# Sapflux-Basic_AltD.net
KiCad netlist of a schematic drawn in EAGLE
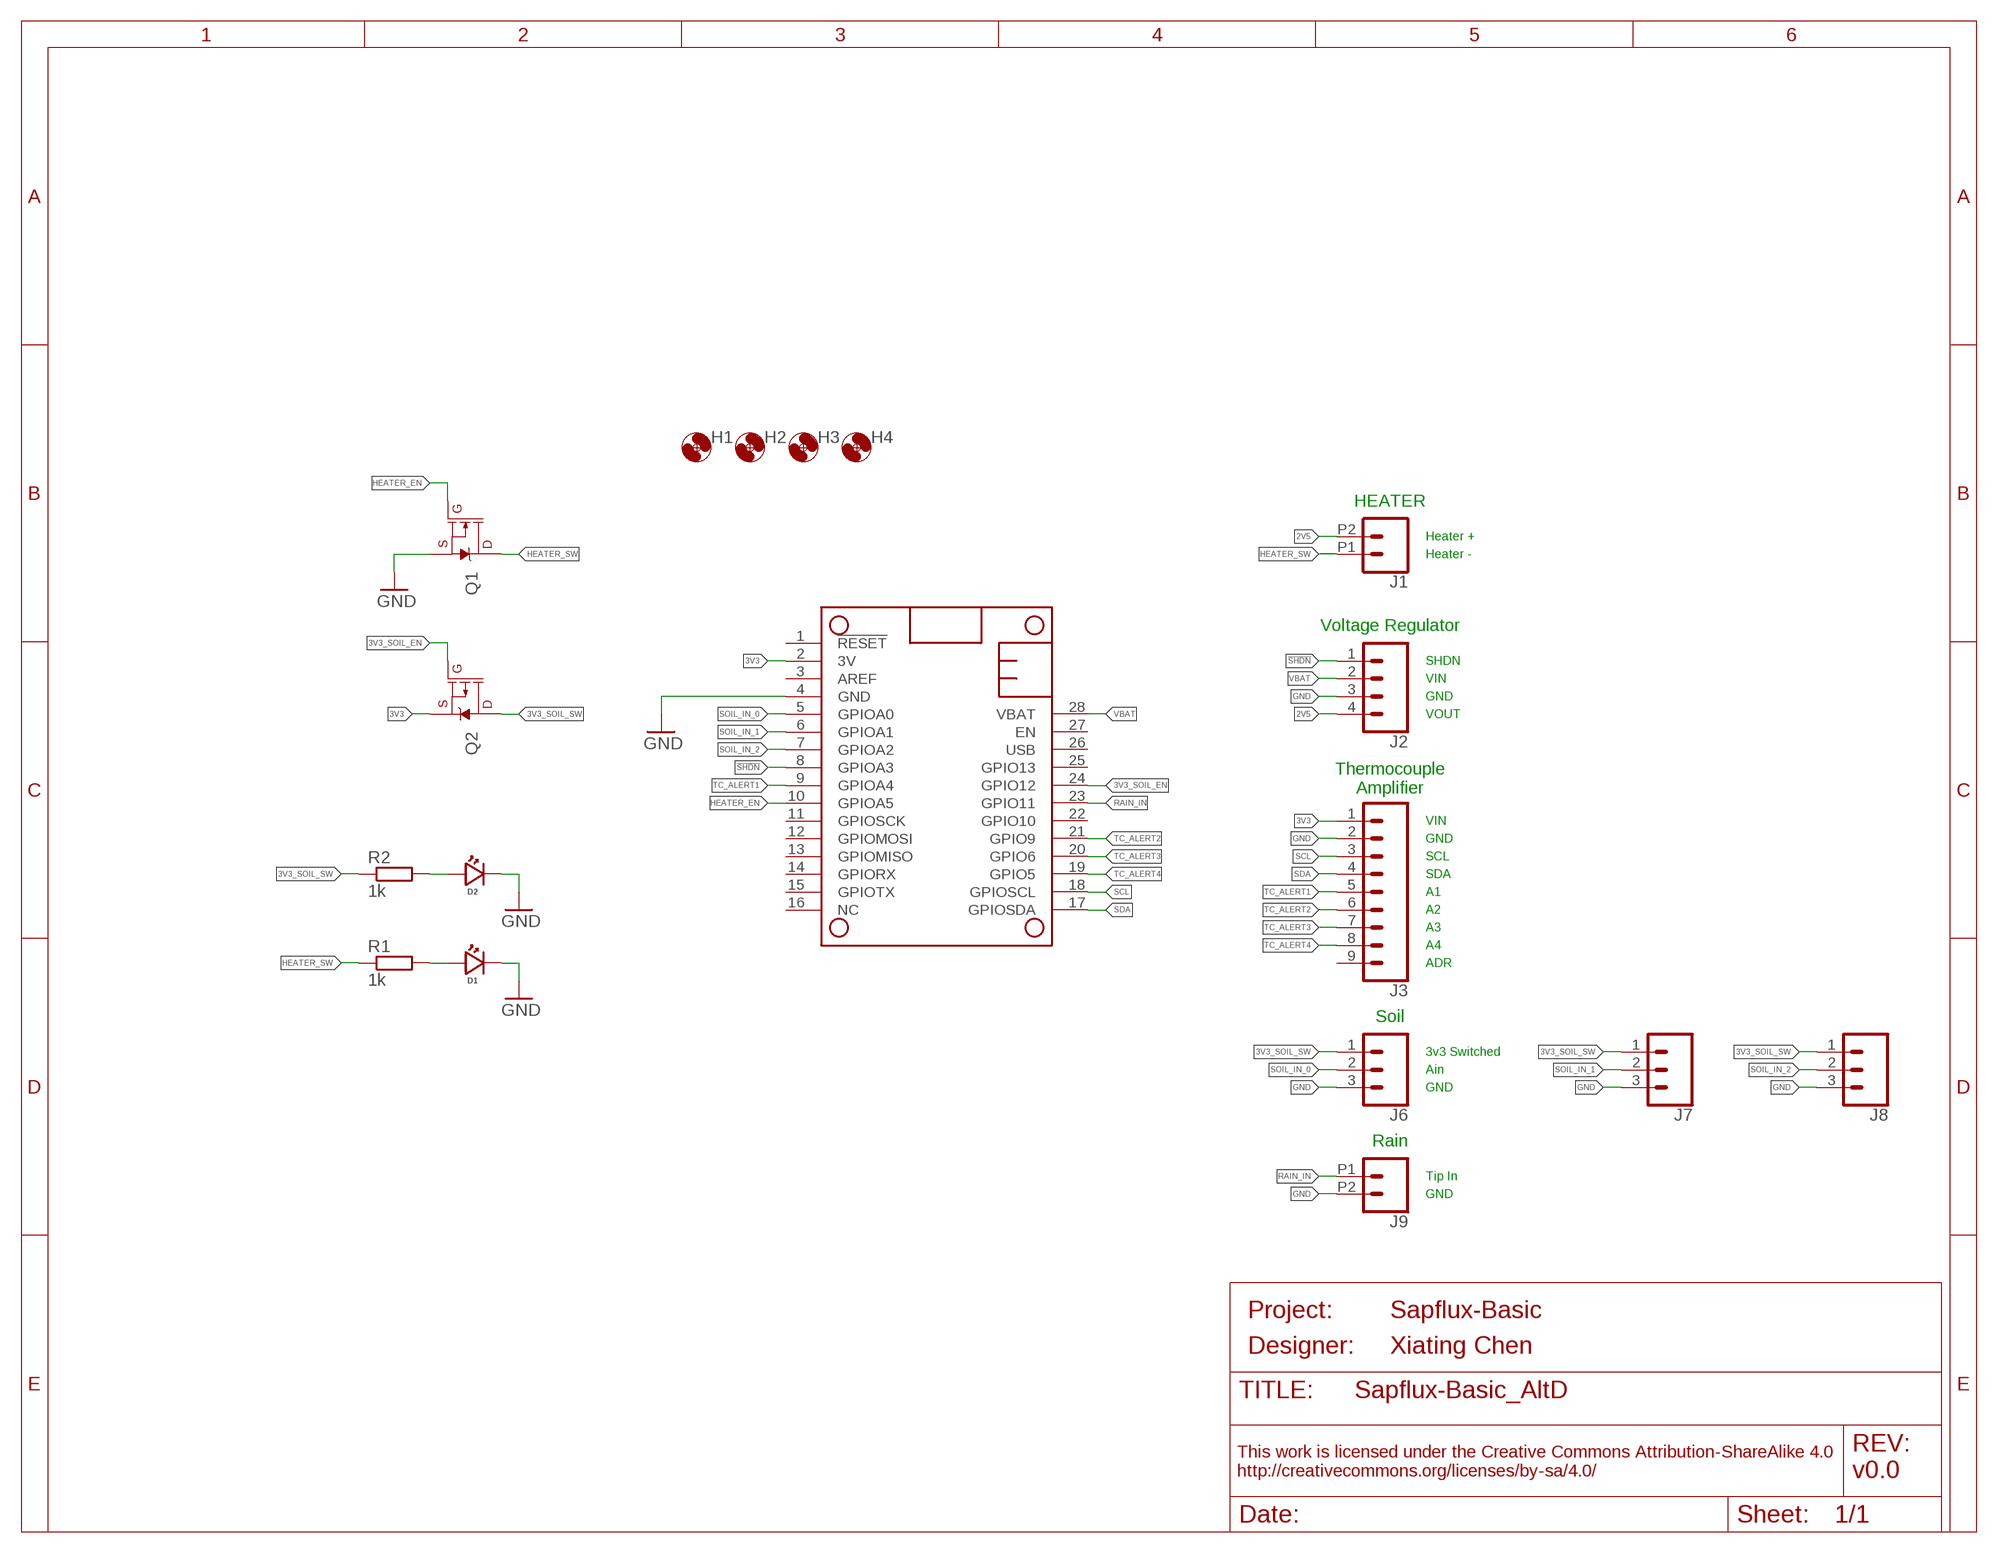
[diagram p0: schematic, sheet 1]

(export (version "E")
  (design (tool "Eeschema 10.0.6"))
  (components
    (comp (ref "D1")
      (value "LED3MM")
      (footprint "eagle-import:LED_3MM")
      (libsource (lib "eagle-import") (part "LED3MM"))
    )
    (comp (ref "D2")
      (value "LED3MM")
      (footprint "eagle-import:LED_3MM")
      (libsource (lib "eagle-import") (part "LED3MM"))
    )
    (comp (ref "H1")
      (value "MOUNTING_HOLE4_NP")
      (footprint "eagle-import:4_40")
      (fields (field (name "MPN") "DNP"))
      (libsource (lib "eagle-import") (part "MOUNTING_HOLE4_NP"))
    )
    (comp (ref "H2")
      (value "MOUNTING_HOLE4_NP")
      (footprint "eagle-import:4_40")
      (fields (field (name "MPN") "DNP"))
      (libsource (lib "eagle-import") (part "MOUNTING_HOLE4_NP"))
    )
    (comp (ref "H3")
      (value "MOUNTING_HOLE4_NP")
      (footprint "eagle-import:4_40")
      (fields (field (name "MPN") "DNP"))
      (libsource (lib "eagle-import") (part "MOUNTING_HOLE4_NP"))
    )
    (comp (ref "H4")
      (value "MOUNTING_HOLE4_NP")
      (footprint "eagle-import:4_40")
      (fields (field (name "MPN") "DNP"))
      (libsource (lib "eagle-import") (part "MOUNTING_HOLE4_NP"))
    )
    (comp (ref "J1")
      (value "CONN_2")
      (footprint "eagle-import:1X02_2.54_SCREWTERM_ROUND")
      (fields (field (name "MF") "OnShore") (field (name "MPN") "OSTVN02A150"))
      (libsource (lib "eagle-import") (part "CONN_022.54_SCREW_ROUND"))
    )
    (comp (ref "J2")
      (value "CONN_42.54")
      (footprint "eagle-import:1X04")
      (fields (field (name "MF") "Adam Tech") (field (name "MPN") "PH1-04-UA"))
      (libsource (lib "eagle-import") (part "CONN_42.54"))
    )
    (comp (ref "J3")
      (value "CONN_9")
      (footprint "eagle-import:1X09")
      (fields (field (name "MF") "Adam Tech") (field (name "MPN") "PH1-09-UA"))
      (libsource (lib "eagle-import") (part "CONN_9"))
    )
    (comp (ref "J6")
      (value "CONN_32.54_SCREW")
      (footprint "eagle-import:1X03_SCREW")
      (fields (field (name "MF") "On Shore") (field (name "MPN") "OSTVN03A150"))
      (libsource (lib "eagle-import") (part "CONN_32.54_SCREW"))
    )
    (comp (ref "J7")
      (value "CONN_32.54_SCREW")
      (footprint "eagle-import:1X03_SCREW")
      (fields (field (name "MF") "On Shore") (field (name "MPN") "OSTVN03A150"))
      (libsource (lib "eagle-import") (part "CONN_32.54_SCREW"))
    )
    (comp (ref "J8")
      (value "CONN_32.54_SCREW")
      (footprint "eagle-import:1X03_SCREW")
      (fields (field (name "MF") "On Shore") (field (name "MPN") "OSTVN03A150"))
      (libsource (lib "eagle-import") (part "CONN_32.54_SCREW"))
    )
    (comp (ref "J9")
      (value "CONN_022.54_SCREW_ROUND")
      (footprint "eagle-import:1X02_2.54_SCREWTERM_ROUND")
      (fields (field (name "MF") "OnShore") (field (name "MPN") "OSTVN02A150"))
      (libsource (lib "eagle-import") (part "CONN_022.54_SCREW_ROUND"))
    )
    (comp (ref "MS1")
      (value "FEATHERWINGLAYOUT")
      (footprint "eagle-import:FEATHERWING_MIN")
      (libsource (lib "eagle-import") (part "FEATHERWINGLAYOUT"))
    )
    (comp (ref "Q1")
      (value "60V/32A/35mΩ")
      (footprint "eagle-import:TO220V")
      (fields (field (name "MF") "Infineon") (field (name "MPN") "IRLB8721PBF"))
      (libsource (lib "eagle-import") (part "MOSFET-NCH-FQP30N06L"))
    )
    (comp (ref "Q2")
      (value "24A/20V/50mΩ")
      (footprint "eagle-import:TO220V")
      (fields (field (name "MF") "Vishay") (field (name "MPN") "SUP53P06-20-E3"))
      (libsource (lib "eagle-import") (part "MOSFET_PCH-NDP6020P"))
    )
    (comp (ref "R1")
      (value "1k")
      (footprint "eagle-import:0204_7")
      (libsource (lib "eagle-import") (part "R-EU_0204/7"))
    )
    (comp (ref "R2")
      (value "1k")
      (footprint "eagle-import:0204_7")
      (libsource (lib "eagle-import") (part "R-EU_0204/7"))
    )
  )
  (nets
    (net (code "1") (name "/USB") (class "Default")
      (node (ref "MS1") (pin "26") (pinfunction "USB_26") (pintype "power_in"))
    )
    (net (code "2") (name "/~{SHDN}") (class "Default")
      (node (ref "J2") (pin "1") (pinfunction "1_1") (pintype "passive"))
      (node (ref "MS1") (pin "8") (pinfunction "GPIOA3_8") (pintype "bidirectional"))
    )
    (net (code "3") (name "2V5") (class "Default")
      (node (ref "J1") (pin "P2") (pinfunction "2_P2") (pintype "passive"))
      (node (ref "J2") (pin "4") (pinfunction "4_4") (pintype "passive"))
    )
    (net (code "4") (name "3V3") (class "Default")
      (node (ref "J3") (pin "1") (pinfunction "1_1") (pintype "passive"))
      (node (ref "MS1") (pin "2") (pinfunction "3V_2") (pintype "power_in"))
      (node (ref "Q2") (pin "3") (pinfunction "S_3") (pintype "bidirectional"))
    )
    (net (code "5") (name "3V3_SOIL_EN") (class "Default")
      (node (ref "MS1") (pin "24") (pinfunction "GPIO12_24") (pintype "bidirectional"))
      (node (ref "Q2") (pin "1") (pinfunction "G_1") (pintype "bidirectional"))
    )
    (net (code "6") (name "3V3_SOIL_SW") (class "Default")
      (node (ref "J6") (pin "1") (pinfunction "1_1") (pintype "passive"))
      (node (ref "J7") (pin "1") (pinfunction "1_1") (pintype "passive"))
      (node (ref "J8") (pin "1") (pinfunction "1_1") (pintype "passive"))
      (node (ref "Q2") (pin "2") (pinfunction "D_2") (pintype "bidirectional"))
      (node (ref "R2") (pin "1") (pinfunction "1_1") (pintype "passive"))
    )
    (net (code "7") (name "GND") (class "Default")
      (node (ref "D1") (pin "2") (pinfunction "CATHODE_2") (pintype "power_in"))
      (node (ref "D2") (pin "2") (pinfunction "CATHODE_2") (pintype "power_in"))
      (node (ref "J2") (pin "3") (pinfunction "3_3") (pintype "passive"))
      (node (ref "J3") (pin "2") (pinfunction "2_2") (pintype "passive"))
      (node (ref "J6") (pin "3") (pinfunction "3_3") (pintype "passive"))
      (node (ref "J7") (pin "3") (pinfunction "3_3") (pintype "passive"))
      (node (ref "J8") (pin "3") (pinfunction "3_3") (pintype "passive"))
      (node (ref "J9") (pin "P2") (pinfunction "2_P2") (pintype "passive"))
      (node (ref "MS1") (pin "4") (pinfunction "GND_4") (pintype "power_in"))
      (node (ref "Q1") (pin "3") (pinfunction "S_3") (pintype "bidirectional"))
    )
    (net (code "8") (name "HEATER_EN") (class "Default")
      (node (ref "MS1") (pin "10") (pinfunction "GPIOA5_10") (pintype "bidirectional"))
      (node (ref "Q1") (pin "1") (pinfunction "G_1") (pintype "bidirectional"))
    )
    (net (code "9") (name "HEATER_SW") (class "Default")
      (node (ref "J1") (pin "P1") (pinfunction "1_P1") (pintype "passive"))
      (node (ref "Q1") (pin "2") (pinfunction "D_2") (pintype "bidirectional"))
      (node (ref "R1") (pin "1") (pinfunction "1_1") (pintype "passive"))
    )
    (net (code "10") (name "Net-(D1-ANODE)") (class "Default")
      (node (ref "D1") (pin "1") (pinfunction "ANODE_1") (pintype "power_in"))
      (node (ref "R1") (pin "2") (pinfunction "2_2") (pintype "passive"))
    )
    (net (code "11") (name "Net-(D2-ANODE)") (class "Default")
      (node (ref "D2") (pin "1") (pinfunction "ANODE_1") (pintype "power_in"))
      (node (ref "R2") (pin "2") (pinfunction "2_2") (pintype "passive"))
    )
    (net (code "12") (name "RAIN_IN") (class "Default")
      (node (ref "J9") (pin "P1") (pinfunction "1_P1") (pintype "passive"))
      (node (ref "MS1") (pin "23") (pinfunction "GPIO11_23") (pintype "bidirectional"))
    )
    (net (code "13") (name "SCL") (class "Default")
      (node (ref "J3") (pin "3") (pinfunction "3_3") (pintype "passive"))
      (node (ref "MS1") (pin "18") (pinfunction "GPIOSCL_18") (pintype "bidirectional"))
    )
    (net (code "14") (name "SDA") (class "Default")
      (node (ref "J3") (pin "4") (pinfunction "4_4") (pintype "passive"))
      (node (ref "MS1") (pin "17") (pinfunction "GPIOSDA_17") (pintype "bidirectional"))
    )
    (net (code "15") (name "SOIL_IN_0") (class "Default")
      (node (ref "J6") (pin "2") (pinfunction "2_2") (pintype "passive"))
      (node (ref "MS1") (pin "5") (pinfunction "GPIOA0_5") (pintype "bidirectional"))
    )
    (net (code "16") (name "SOIL_IN_1") (class "Default")
      (node (ref "J7") (pin "2") (pinfunction "2_2") (pintype "passive"))
      (node (ref "MS1") (pin "6") (pinfunction "GPIOA1_6") (pintype "bidirectional"))
    )
    (net (code "17") (name "SOIL_IN_2") (class "Default")
      (node (ref "J8") (pin "2") (pinfunction "2_2") (pintype "passive"))
      (node (ref "MS1") (pin "7") (pinfunction "GPIOA2_7") (pintype "bidirectional"))
    )
    (net (code "18") (name "TC_ALERT1") (class "Default")
      (node (ref "J3") (pin "5") (pinfunction "5_5") (pintype "passive"))
      (node (ref "MS1") (pin "9") (pinfunction "GPIOA4_9") (pintype "bidirectional"))
    )
    (net (code "19") (name "TC_ALERT2") (class "Default")
      (node (ref "J3") (pin "6") (pinfunction "6_6") (pintype "passive"))
      (node (ref "MS1") (pin "21") (pinfunction "GPIO9_21") (pintype "bidirectional"))
    )
    (net (code "20") (name "TC_ALERT3") (class "Default")
      (node (ref "J3") (pin "7") (pinfunction "7_7") (pintype "passive"))
      (node (ref "MS1") (pin "20") (pinfunction "GPIO6_20") (pintype "bidirectional"))
    )
    (net (code "21") (name "TC_ALERT4") (class "Default")
      (node (ref "J3") (pin "8") (pinfunction "8_8") (pintype "passive"))
      (node (ref "MS1") (pin "19") (pinfunction "GPIO5_19") (pintype "bidirectional"))
    )
    (net (code "22") (name "VBAT") (class "Default")
      (node (ref "J2") (pin "2") (pinfunction "2_2") (pintype "passive"))
      (node (ref "MS1") (pin "28") (pinfunction "VBAT_28") (pintype "power_in"))
    )
    (net (code "23") (name "unconnected-(J3-Pad9)") (class "Default")
      (node (ref "J3") (pin "9") (pinfunction "9_9") (pintype "passive"))
    )
    (net (code "24") (name "unconnected-(MS1-AREF-Pad3)") (class "Default")
      (node (ref "MS1") (pin "3") (pinfunction "AREF_3") (pintype "passive"))
    )
    (net (code "25") (name "unconnected-(MS1-EN-Pad27)") (class "Default")
      (node (ref "MS1") (pin "27") (pinfunction "EN_27") (pintype "passive"))
    )
    (net (code "26") (name "unconnected-(MS1-GPIO10-Pad22)") (class "Default")
      (node (ref "MS1") (pin "22") (pinfunction "GPIO10_22") (pintype "bidirectional"))
    )
    (net (code "27") (name "unconnected-(MS1-GPIO13-Pad25)") (class "Default")
      (node (ref "MS1") (pin "25") (pinfunction "GPIO13_25") (pintype "bidirectional"))
    )
    (net (code "28") (name "unconnected-(MS1-GPIOMISO-Pad13)") (class "Default")
      (node (ref "MS1") (pin "13") (pinfunction "GPIOMISO_13") (pintype "bidirectional"))
    )
    (net (code "29") (name "unconnected-(MS1-GPIOMOSI-Pad12)") (class "Default")
      (node (ref "MS1") (pin "12") (pinfunction "GPIOMOSI_12") (pintype "bidirectional"))
    )
    (net (code "30") (name "unconnected-(MS1-GPIORX-Pad14)") (class "Default")
      (node (ref "MS1") (pin "14") (pinfunction "GPIORX_14") (pintype "bidirectional"))
    )
    (net (code "31") (name "unconnected-(MS1-GPIOSCK-Pad11)") (class "Default")
      (node (ref "MS1") (pin "11") (pinfunction "GPIOSCK_11") (pintype "bidirectional"))
    )
    (net (code "32") (name "unconnected-(MS1-GPIOTX-Pad15)") (class "Default")
      (node (ref "MS1") (pin "15") (pinfunction "GPIOTX_15") (pintype "bidirectional"))
    )
    (net (code "33") (name "unconnected-(MS1-NC-Pad16)") (class "Default")
      (node (ref "MS1") (pin "16") (pinfunction "NC_16") (pintype "passive"))
    )
    (net (code "34") (name "unconnected-(MS1-~{RESET}-Pad1)") (class "Default")
      (node (ref "MS1") (pin "1") (pinfunction "~{RESET}_1") (pintype "input"))
    )
  )
)
